# MAXIM-ADC1.net
KiCad netlist of a schematic drawn in Altium Designer
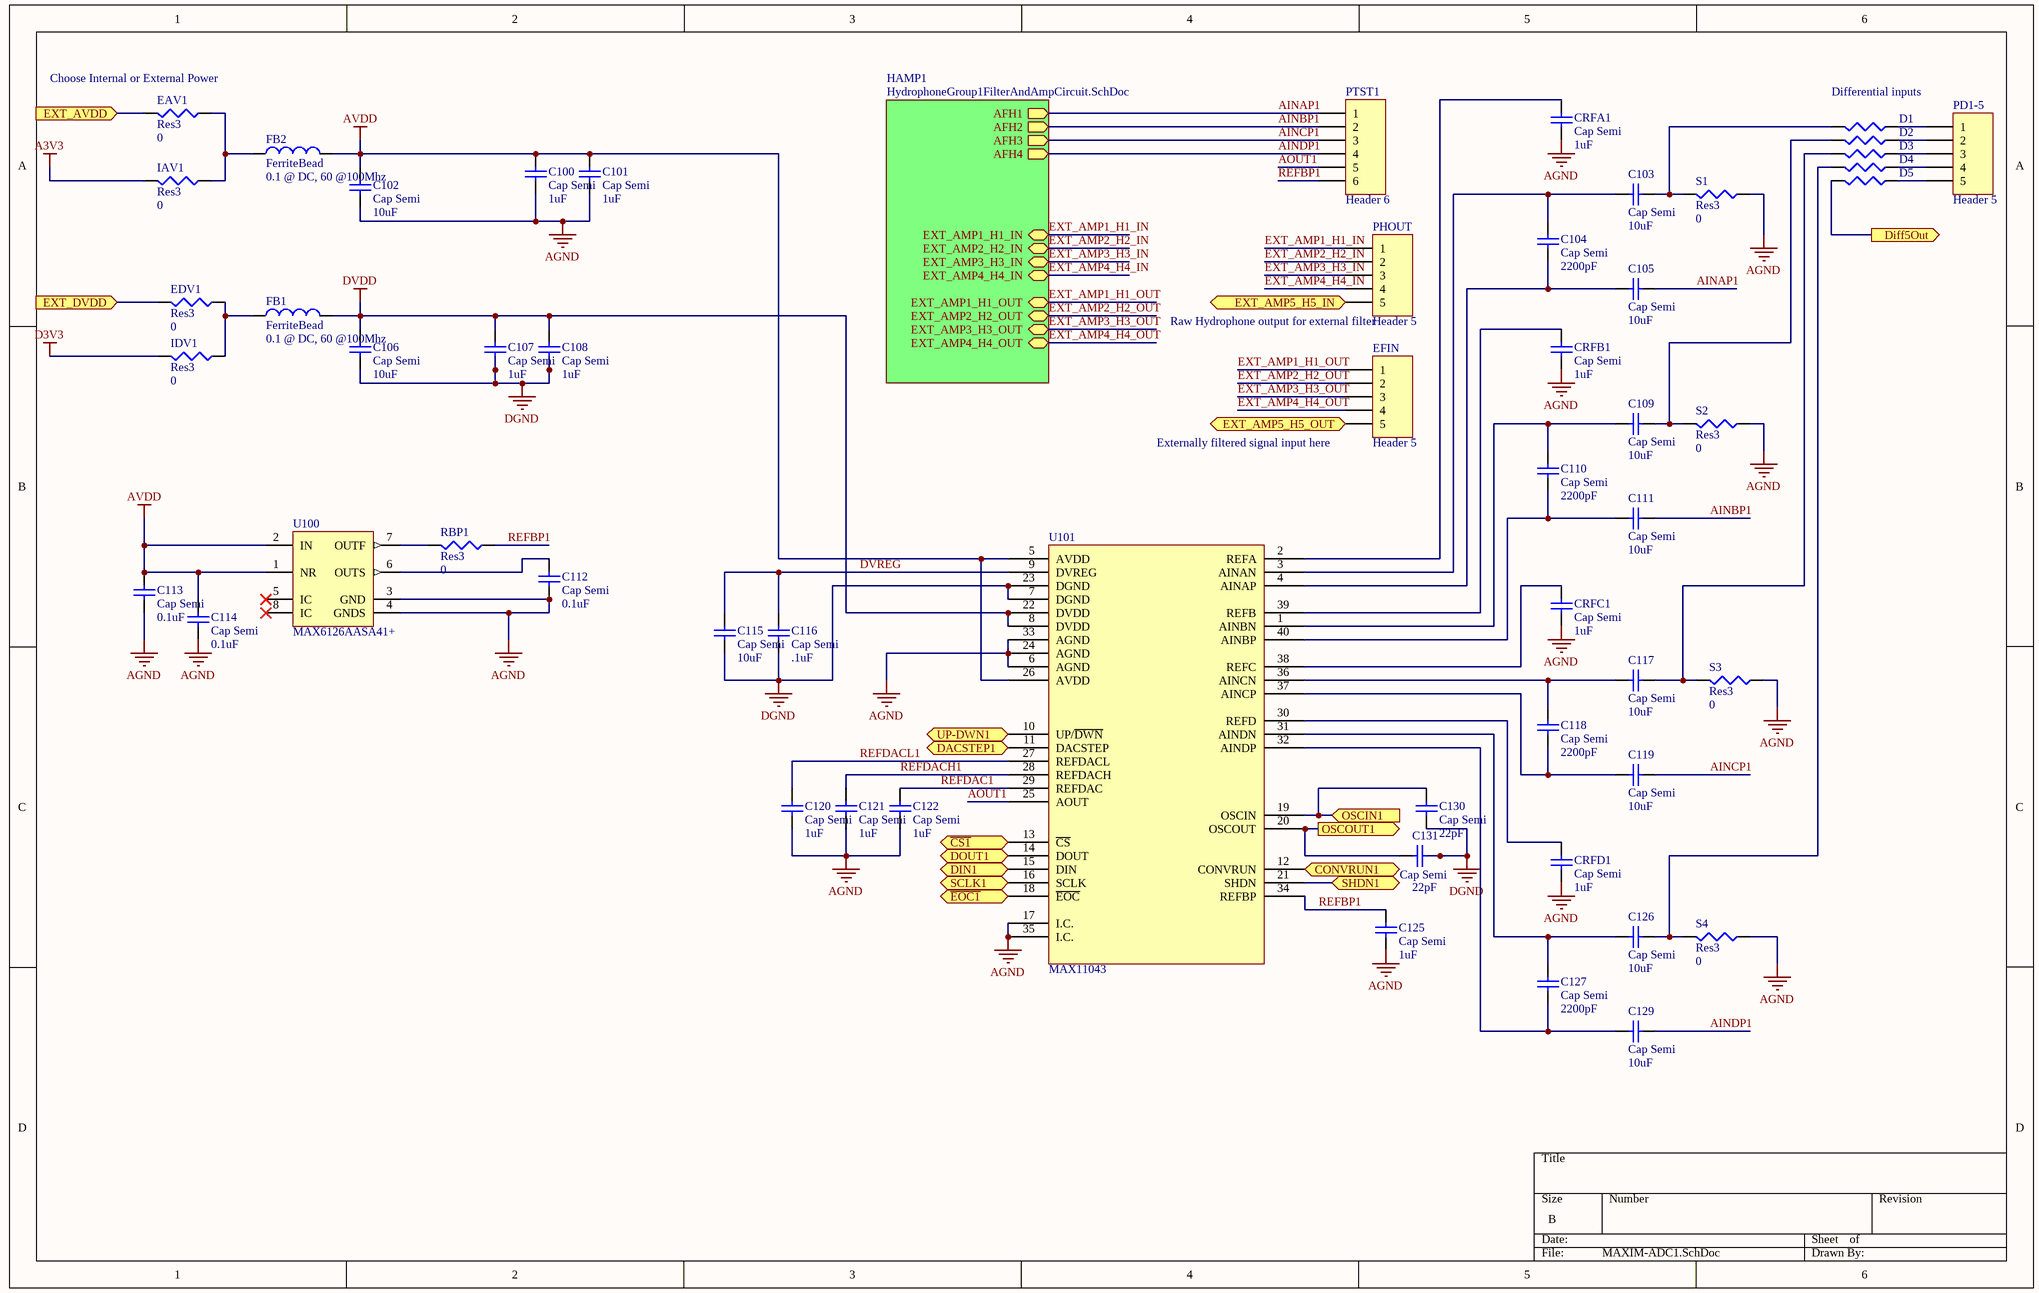
[diagram p0: MAXIM-ADC1.SchDoc]

(export (version "E")
  (design (tool "Eeschema 10.0.6"))
  (components
    (comp (ref "C100")
      (value "Cap Semi")
      (footprint "1608[0603]")
      (description "Capacitor (Semiconductor SIM Model)")
      (fields (field (name "ALTIUM_VALUE") "1uF") (field (name "PUBLISHER") "Altium Limited"))
      (libsource (lib "Miscellaneous Devices") (part "Cap Semi"))
    )
    (comp (ref "C101")
      (value "Cap Semi")
      (footprint "1608[0603]")
      (description "Capacitor (Semiconductor SIM Model)")
      (fields (field (name "ALTIUM_VALUE") "1uF") (field (name "PUBLISHER") "Altium Limited"))
      (libsource (lib "Miscellaneous Devices") (part "Cap Semi"))
    )
    (comp (ref "C102")
      (value "Cap Semi")
      (footprint "1608[0603]")
      (description "Capacitor (Semiconductor SIM Model)")
      (fields (field (name "ALTIUM_VALUE") "10uF") (field (name "PUBLISHER") "Altium Limited"))
      (libsource (lib "Miscellaneous Devices") (part "Cap Semi"))
    )
    (comp (ref "C103")
      (value "Cap Semi")
      (footprint "1608[0603]")
      (description "Capacitor (Semiconductor SIM Model)")
      (fields (field (name "ALTIUM_VALUE") "10uF") (field (name "PUBLISHER") "Altium Limited"))
      (libsource (lib "Miscellaneous Devices") (part "Cap Semi"))
    )
    (comp (ref "C104")
      (value "Cap Semi")
      (footprint "1608[0603]")
      (description "Capacitor (Semiconductor SIM Model)")
      (fields (field (name "ALTIUM_VALUE") "2200pF") (field (name "PUBLISHER") "Altium Limited"))
      (libsource (lib "Miscellaneous Devices") (part "Cap Semi"))
    )
    (comp (ref "C105")
      (value "Cap Semi")
      (footprint "1608[0603]")
      (description "Capacitor (Semiconductor SIM Model)")
      (fields (field (name "ALTIUM_VALUE") "10uF") (field (name "PUBLISHER") "Altium Limited"))
      (libsource (lib "Miscellaneous Devices") (part "Cap Semi"))
    )
    (comp (ref "C106")
      (value "Cap Semi")
      (footprint "1608[0603]")
      (description "Capacitor (Semiconductor SIM Model)")
      (fields (field (name "ALTIUM_VALUE") "10uF") (field (name "PUBLISHER") "Altium Limited"))
      (libsource (lib "Miscellaneous Devices") (part "Cap Semi"))
    )
    (comp (ref "C107")
      (value "Cap Semi")
      (footprint "1608[0603]")
      (description "Capacitor (Semiconductor SIM Model)")
      (fields (field (name "ALTIUM_VALUE") "1uF") (field (name "PUBLISHER") "Altium Limited"))
      (libsource (lib "Miscellaneous Devices") (part "Cap Semi"))
    )
    (comp (ref "C108")
      (value "Cap Semi")
      (footprint "1608[0603]")
      (description "Capacitor (Semiconductor SIM Model)")
      (fields (field (name "ALTIUM_VALUE") "1uF") (field (name "PUBLISHER") "Altium Limited"))
      (libsource (lib "Miscellaneous Devices") (part "Cap Semi"))
    )
    (comp (ref "C109")
      (value "Cap Semi")
      (footprint "1608[0603]")
      (description "Capacitor (Semiconductor SIM Model)")
      (fields (field (name "ALTIUM_VALUE") "10uF") (field (name "PUBLISHER") "Altium Limited"))
      (libsource (lib "Miscellaneous Devices") (part "Cap Semi"))
    )
    (comp (ref "C110")
      (value "Cap Semi")
      (footprint "1608[0603]")
      (description "Capacitor (Semiconductor SIM Model)")
      (fields (field (name "ALTIUM_VALUE") "2200pF") (field (name "PUBLISHER") "Altium Limited"))
      (libsource (lib "Miscellaneous Devices") (part "Cap Semi"))
    )
    (comp (ref "C111")
      (value "Cap Semi")
      (footprint "1608[0603]")
      (description "Capacitor (Semiconductor SIM Model)")
      (fields (field (name "ALTIUM_VALUE") "10uF") (field (name "PUBLISHER") "Altium Limited"))
      (libsource (lib "Miscellaneous Devices") (part "Cap Semi"))
    )
    (comp (ref "C112")
      (value "Cap Semi")
      (footprint "1608[0603]")
      (description "Capacitor (Semiconductor SIM Model)")
      (fields (field (name "ALTIUM_VALUE") "0.1uF") (field (name "PUBLISHER") "Altium Limited"))
      (libsource (lib "Miscellaneous Devices") (part "Cap Semi"))
    )
    (comp (ref "C113")
      (value "Cap Semi")
      (footprint "1608[0603]")
      (description "Capacitor (Semiconductor SIM Model)")
      (fields (field (name "ALTIUM_VALUE") "0.1uF") (field (name "PUBLISHER") "Altium Limited"))
      (libsource (lib "Miscellaneous Devices") (part "Cap Semi"))
    )
    (comp (ref "C114")
      (value "Cap Semi")
      (footprint "1608[0603]")
      (description "Capacitor (Semiconductor SIM Model)")
      (fields (field (name "ALTIUM_VALUE") "0.1uF") (field (name "PUBLISHER") "Altium Limited"))
      (libsource (lib "Miscellaneous Devices") (part "Cap Semi"))
    )
    (comp (ref "C115")
      (value "Cap Semi")
      (footprint "1608[0603]")
      (description "Capacitor (Semiconductor SIM Model)")
      (fields (field (name "ALTIUM_VALUE") "10uF") (field (name "PUBLISHER") "Altium Limited"))
      (libsource (lib "Miscellaneous Devices") (part "Cap Semi"))
    )
    (comp (ref "C116")
      (value "Cap Semi")
      (footprint "1608[0603]")
      (description "Capacitor (Semiconductor SIM Model)")
      (fields (field (name "ALTIUM_VALUE") ".1uF") (field (name "PUBLISHER") "Altium Limited"))
      (libsource (lib "Miscellaneous Devices") (part "Cap Semi"))
    )
    (comp (ref "C117")
      (value "Cap Semi")
      (footprint "1608[0603]")
      (description "Capacitor (Semiconductor SIM Model)")
      (fields (field (name "ALTIUM_VALUE") "10uF") (field (name "PUBLISHER") "Altium Limited"))
      (libsource (lib "Miscellaneous Devices") (part "Cap Semi"))
    )
    (comp (ref "C118")
      (value "Cap Semi")
      (footprint "1608[0603]")
      (description "Capacitor (Semiconductor SIM Model)")
      (fields (field (name "ALTIUM_VALUE") "2200pF") (field (name "PUBLISHER") "Altium Limited"))
      (libsource (lib "Miscellaneous Devices") (part "Cap Semi"))
    )
    (comp (ref "C119")
      (value "Cap Semi")
      (footprint "1608[0603]")
      (description "Capacitor (Semiconductor SIM Model)")
      (fields (field (name "ALTIUM_VALUE") "10uF") (field (name "PUBLISHER") "Altium Limited"))
      (libsource (lib "Miscellaneous Devices") (part "Cap Semi"))
    )
    (comp (ref "C120")
      (value "Cap Semi")
      (footprint "1608[0603]")
      (description "Capacitor (Semiconductor SIM Model)")
      (fields (field (name "ALTIUM_VALUE") "1uF") (field (name "PUBLISHER") "Altium Limited"))
      (libsource (lib "Miscellaneous Devices") (part "Cap Semi"))
    )
    (comp (ref "C121")
      (value "Cap Semi")
      (footprint "1608[0603]")
      (description "Capacitor (Semiconductor SIM Model)")
      (fields (field (name "ALTIUM_VALUE") "1uF") (field (name "PUBLISHER") "Altium Limited"))
      (libsource (lib "Miscellaneous Devices") (part "Cap Semi"))
    )
    (comp (ref "C122")
      (value "Cap Semi")
      (footprint "1608[0603]")
      (description "Capacitor (Semiconductor SIM Model)")
      (fields (field (name "ALTIUM_VALUE") "1uF") (field (name "PUBLISHER") "Altium Limited"))
      (libsource (lib "Miscellaneous Devices") (part "Cap Semi"))
    )
    (comp (ref "C125")
      (value "Cap Semi")
      (footprint "1608[0603]")
      (description "Capacitor (Semiconductor SIM Model)")
      (fields (field (name "ALTIUM_VALUE") "1uF") (field (name "PUBLISHER") "Altium Limited"))
      (libsource (lib "Miscellaneous Devices") (part "Cap Semi"))
    )
    (comp (ref "C126")
      (value "Cap Semi")
      (footprint "1608[0603]")
      (description "Capacitor (Semiconductor SIM Model)")
      (fields (field (name "ALTIUM_VALUE") "10uF") (field (name "PUBLISHER") "Altium Limited"))
      (libsource (lib "Miscellaneous Devices") (part "Cap Semi"))
    )
    (comp (ref "C127")
      (value "Cap Semi")
      (footprint "1608[0603]")
      (description "Capacitor (Semiconductor SIM Model)")
      (fields (field (name "ALTIUM_VALUE") "2200pF") (field (name "PUBLISHER") "Altium Limited"))
      (libsource (lib "Miscellaneous Devices") (part "Cap Semi"))
    )
    (comp (ref "C129")
      (value "Cap Semi")
      (footprint "1608[0603]")
      (description "Capacitor (Semiconductor SIM Model)")
      (fields (field (name "ALTIUM_VALUE") "10uF") (field (name "PUBLISHER") "Altium Limited"))
      (libsource (lib "Miscellaneous Devices") (part "Cap Semi"))
    )
    (comp (ref "C130")
      (value "Cap Semi")
      (footprint "1608[0603]")
      (description "Capacitor (Semiconductor SIM Model)")
      (fields (field (name "ALTIUM_VALUE") "22pF") (field (name "PUBLISHER") "Altium Limited"))
      (libsource (lib "Miscellaneous Devices") (part "Cap Semi"))
    )
    (comp (ref "C131")
      (value "Cap Semi")
      (footprint "1608[0603]")
      (description "Capacitor (Semiconductor SIM Model)")
      (fields (field (name "ALTIUM_VALUE") "22pF") (field (name "PUBLISHER") "Altium Limited"))
      (libsource (lib "Miscellaneous Devices") (part "Cap Semi"))
    )
    (comp (ref "CRFA1")
      (value "Cap Semi")
      (footprint "1608[0603]")
      (description "Capacitor (Semiconductor SIM Model)")
      (fields (field (name "ALTIUM_VALUE") "1uF") (field (name "PUBLISHER") "Altium Limited"))
      (libsource (lib "Miscellaneous Devices") (part "Cap Semi"))
    )
    (comp (ref "CRFB1")
      (value "Cap Semi")
      (footprint "1608[0603]")
      (description "Capacitor (Semiconductor SIM Model)")
      (fields (field (name "ALTIUM_VALUE") "1uF") (field (name "PUBLISHER") "Altium Limited"))
      (libsource (lib "Miscellaneous Devices") (part "Cap Semi"))
    )
    (comp (ref "CRFC1")
      (value "Cap Semi")
      (footprint "1608[0603]")
      (description "Capacitor (Semiconductor SIM Model)")
      (fields (field (name "ALTIUM_VALUE") "1uF") (field (name "PUBLISHER") "Altium Limited"))
      (libsource (lib "Miscellaneous Devices") (part "Cap Semi"))
    )
    (comp (ref "CRFD1")
      (value "Cap Semi")
      (footprint "1608[0603]")
      (description "Capacitor (Semiconductor SIM Model)")
      (fields (field (name "ALTIUM_VALUE") "1uF") (field (name "PUBLISHER") "Altium Limited"))
      (libsource (lib "Miscellaneous Devices") (part "Cap Semi"))
    )
    (comp (ref "D1")
      (value "Res3")
      (footprint "J1-0603")
      (description "Resistor")
      (fields (field (name "PUBLISHER") "Altium Limited"))
      (libsource (lib "Miscellaneous Devices") (part "Res3"))
    )
    (comp (ref "D2")
      (value "Res3")
      (footprint "J1-0603")
      (description "Resistor")
      (fields (field (name "PUBLISHER") "Altium Limited"))
      (libsource (lib "Miscellaneous Devices") (part "Res3"))
    )
    (comp (ref "D3")
      (value "Res3")
      (footprint "J1-0603")
      (description "Resistor")
      (fields (field (name "PUBLISHER") "Altium Limited"))
      (libsource (lib "Miscellaneous Devices") (part "Res3"))
    )
    (comp (ref "D4")
      (value "Res3")
      (footprint "J1-0603")
      (description "Resistor")
      (fields (field (name "PUBLISHER") "Altium Limited"))
      (libsource (lib "Miscellaneous Devices") (part "Res3"))
    )
    (comp (ref "D5")
      (value "Res3")
      (footprint "J1-0603")
      (description "Resistor")
      (fields (field (name "PUBLISHER") "Altium Limited"))
      (libsource (lib "Miscellaneous Devices") (part "Res3"))
    )
    (comp (ref "EAV1")
      (value "Res3")
      (footprint "J1-0603")
      (description "Resistor")
      (fields (field (name "ALTIUM_VALUE") "0") (field (name "PUBLISHER") "Altium Limited"))
      (libsource (lib "Miscellaneous Devices") (part "Res3"))
    )
    (comp (ref "EDV1")
      (value "Res3")
      (footprint "J1-0603")
      (description "Resistor")
      (fields (field (name "ALTIUM_VALUE") "0") (field (name "PUBLISHER") "Altium Limited"))
      (libsource (lib "Miscellaneous Devices") (part "Res3"))
    )
    (comp (ref "EFIN")
      (value "Header 5")
      (footprint "HDR1X5")
      (description "Header, 5-Pin")
      (fields (field (name "PUBLISHER") "Altium Limited"))
      (libsource (lib "Miscellaneous Connectors") (part "Header 5"))
    )
    (comp (ref "FB1")
      (value "FerriteBead")
      (footprint "0603")
      (description "Inductor")
      (fields
        (field (name "ALTIUM_VALUE") "0.1 @ DC, 60 @100Mhz")
        (field (name "PUBLISHER") "Altium Limited")
      )
      (libsource (lib "Miscellaneous Devices") (part "Inductor"))
    )
    (comp (ref "FB2")
      (value "FerriteBead")
      (footprint "0603")
      (description "Inductor")
      (fields
        (field (name "ALTIUM_VALUE") "0.1 @ DC, 60 @100Mhz")
        (field (name "PUBLISHER") "Altium Limited")
      )
      (libsource (lib "Miscellaneous Devices") (part "Inductor"))
    )
    (comp (ref "IAV1")
      (value "Res3")
      (footprint "J1-0603")
      (description "Resistor")
      (fields (field (name "ALTIUM_VALUE") "0") (field (name "PUBLISHER") "Altium Limited"))
      (libsource (lib "Miscellaneous Devices") (part "Res3"))
    )
    (comp (ref "IDV1")
      (value "Res3")
      (footprint "J1-0603")
      (description "Resistor")
      (fields (field (name "ALTIUM_VALUE") "0") (field (name "PUBLISHER") "Altium Limited"))
      (libsource (lib "Miscellaneous Devices") (part "Res3"))
    )
    (comp (ref "PD1-5")
      (value "Header 5")
      (footprint "HDR1X5")
      (description "Header, 5-Pin")
      (fields (field (name "PUBLISHER") "Altium Limited"))
      (libsource (lib "Miscellaneous Connectors") (part "Header 5"))
    )
    (comp (ref "PHOUT")
      (value "Header 5")
      (footprint "HDR1X5")
      (description "Header, 5-Pin")
      (fields (field (name "PUBLISHER") "Altium Limited"))
      (libsource (lib "Miscellaneous Connectors") (part "Header 5"))
    )
    (comp (ref "PTST1")
      (value "Header 6")
      (footprint "HDR1X6")
      (description "ADC1 signal test")
      (fields (field (name "PUBLISHER") "Altium Limited"))
      (libsource (lib "Miscellaneous Connectors") (part "Header 6"))
    )
    (comp (ref "RBP1")
      (value "Res3")
      (footprint "J1-0603")
      (description "Resistor")
      (fields (field (name "ALTIUM_VALUE") "0") (field (name "PUBLISHER") "Altium Limited"))
      (libsource (lib "Miscellaneous Devices") (part "Res3"))
    )
    (comp (ref "S1")
      (value "Res3")
      (footprint "J1-0603")
      (description "Resistor")
      (fields (field (name "ALTIUM_VALUE") "0") (field (name "PUBLISHER") "Altium Limited"))
      (libsource (lib "Miscellaneous Devices") (part "Res3"))
    )
    (comp (ref "S2")
      (value "Res3")
      (footprint "J1-0603")
      (description "Resistor")
      (fields (field (name "ALTIUM_VALUE") "0") (field (name "PUBLISHER") "Altium Limited"))
      (libsource (lib "Miscellaneous Devices") (part "Res3"))
    )
    (comp (ref "S3")
      (value "Res3")
      (footprint "J1-0603")
      (description "Resistor")
      (fields (field (name "ALTIUM_VALUE") "0") (field (name "PUBLISHER") "Altium Limited"))
      (libsource (lib "Miscellaneous Devices") (part "Res3"))
    )
    (comp (ref "S4")
      (value "Res3")
      (footprint "J1-0603")
      (description "Resistor")
      (fields (field (name "ALTIUM_VALUE") "0") (field (name "PUBLISHER") "Altium Limited"))
      (libsource (lib "Miscellaneous Devices") (part "Res3"))
    )
    (comp (ref "U100")
      (value "MAX6126AASA41+")
      (footprint "MAXM-S8+4_L")
      (fields (field (name "MANUFACTURER") "Maxim"))
      (libsource (lib "Altium Content Vault") (part "CMP-0977-00016-1"))
    )
    (comp (ref "U101")
      (value "MAX11043")
      (footprint "QFN50P600X600X80_HS-41N")
      (libsource (lib "Max11043") (part "MAX11043"))
    )
  )
  (nets
    (net (code "1") (name "/AINAP1") (class "Default")
      (node (ref "C105") (pin "1") (pinfunction "1_1") (pintype "passive"))
      (node (ref "PTST1") (pin "1") (pinfunction "1_1") (pintype "passive"))
    )
    (net (code "2") (name "/AINBP1") (class "Default")
      (node (ref "C111") (pin "1") (pinfunction "1_1") (pintype "passive"))
      (node (ref "PTST1") (pin "2") (pinfunction "2_2") (pintype "passive"))
    )
    (net (code "3") (name "/AINCP1") (class "Default")
      (node (ref "C119") (pin "1") (pinfunction "1_1") (pintype "passive"))
      (node (ref "PTST1") (pin "3") (pinfunction "3_3") (pintype "passive"))
    )
    (net (code "4") (name "/AINDP1") (class "Default")
      (node (ref "C129") (pin "1") (pinfunction "1_1") (pintype "passive"))
      (node (ref "PTST1") (pin "4") (pinfunction "4_4") (pintype "passive"))
    )
    (net (code "5") (name "/AOUT1") (class "Default")
      (node (ref "PTST1") (pin "5") (pinfunction "5_5") (pintype "passive"))
      (node (ref "U101") (pin "25") (pinfunction "AOUT_25") (pintype "passive"))
    )
    (net (code "6") (name "/CONVRUN1") (class "Default")
      (node (ref "U101") (pin "12") (pinfunction "CONVRUN_12") (pintype "passive"))
    )
    (net (code "7") (name "/DACSTEP1") (class "Default")
      (node (ref "U101") (pin "11") (pinfunction "DACSTEP_11") (pintype "passive"))
    )
    (net (code "8") (name "/DIN1") (class "Default")
      (node (ref "U101") (pin "15") (pinfunction "DIN_15") (pintype "passive"))
    )
    (net (code "9") (name "/DOUT1") (class "Default")
      (node (ref "U101") (pin "14") (pinfunction "DOUT_14") (pintype "passive"))
    )
    (net (code "10") (name "/DVREG") (class "Default")
      (node (ref "C115") (pin "1") (pinfunction "1_1") (pintype "passive"))
      (node (ref "C116") (pin "1") (pinfunction "1_1") (pintype "passive"))
      (node (ref "U101") (pin "9") (pinfunction "DVREG_9") (pintype "passive"))
    )
    (net (code "11") (name "/Diff5Out") (class "Default")
      (node (ref "D5") (pin "2") (pinfunction "2_2") (pintype "passive"))
    )
    (net (code "12") (name "/EXT_AMP1_H1_IN") (class "Default")
      (node (ref "PHOUT") (pin "1") (pinfunction "1_1") (pintype "passive"))
    )
    (net (code "13") (name "/EXT_AMP1_H1_OUT") (class "Default")
      (node (ref "EFIN") (pin "1") (pinfunction "1_1") (pintype "passive"))
    )
    (net (code "14") (name "/EXT_AMP2_H2_IN") (class "Default")
      (node (ref "PHOUT") (pin "2") (pinfunction "2_2") (pintype "passive"))
    )
    (net (code "15") (name "/EXT_AMP2_H2_OUT") (class "Default")
      (node (ref "EFIN") (pin "2") (pinfunction "2_2") (pintype "passive"))
    )
    (net (code "16") (name "/EXT_AMP3_H3_IN") (class "Default")
      (node (ref "PHOUT") (pin "3") (pinfunction "3_3") (pintype "passive"))
    )
    (net (code "17") (name "/EXT_AMP3_H3_OUT") (class "Default")
      (node (ref "EFIN") (pin "3") (pinfunction "3_3") (pintype "passive"))
    )
    (net (code "18") (name "/EXT_AMP4_H4_IN") (class "Default")
      (node (ref "PHOUT") (pin "4") (pinfunction "4_4") (pintype "passive"))
    )
    (net (code "19") (name "/EXT_AMP4_H4_OUT") (class "Default")
      (node (ref "EFIN") (pin "4") (pinfunction "4_4") (pintype "passive"))
    )
    (net (code "20") (name "/EXT_AMP5_H5_IN") (class "Default")
      (node (ref "PHOUT") (pin "5") (pinfunction "5_5") (pintype "passive"))
    )
    (net (code "21") (name "/EXT_AMP5_H5_OUT") (class "Default")
      (node (ref "EFIN") (pin "5") (pinfunction "5_5") (pintype "passive"))
    )
    (net (code "22") (name "/EXT_AVDD") (class "Default")
      (node (ref "EAV1") (pin "2") (pinfunction "2_2") (pintype "passive"))
    )
    (net (code "23") (name "/EXT_DVDD") (class "Default")
      (node (ref "EDV1") (pin "2") (pinfunction "2_2") (pintype "passive"))
    )
    (net (code "24") (name "/OSCIN1") (class "Default")
      (node (ref "C130") (pin "1") (pinfunction "1_1") (pintype "passive"))
      (node (ref "U101") (pin "19") (pinfunction "OSCIN_19") (pintype "passive"))
    )
    (net (code "25") (name "/OSCOUT1") (class "Default")
      (node (ref "C131") (pin "1") (pinfunction "1_1") (pintype "passive"))
      (node (ref "U101") (pin "20") (pinfunction "OSCOUT_20") (pintype "passive"))
    )
    (net (code "26") (name "/REFBP1") (class "Default")
      (node (ref "C125") (pin "1") (pinfunction "1_1") (pintype "passive"))
      (node (ref "PTST1") (pin "6") (pinfunction "6_6") (pintype "passive"))
      (node (ref "RBP1") (pin "1") (pinfunction "1_1") (pintype "passive"))
      (node (ref "U101") (pin "34") (pinfunction "REFBP_34") (pintype "passive"))
    )
    (net (code "27") (name "/REFDAC1") (class "Default")
      (node (ref "C122") (pin "2") (pinfunction "2_2") (pintype "passive"))
      (node (ref "U101") (pin "29") (pinfunction "REFDAC_29") (pintype "passive"))
    )
    (net (code "28") (name "/REFDACH1") (class "Default")
      (node (ref "C121") (pin "1") (pinfunction "1_1") (pintype "passive"))
      (node (ref "U101") (pin "28") (pinfunction "REFDACH_28") (pintype "passive"))
    )
    (net (code "29") (name "/REFDACL1") (class "Default")
      (node (ref "C120") (pin "2") (pinfunction "2_2") (pintype "passive"))
      (node (ref "U101") (pin "27") (pinfunction "REFDACL_27") (pintype "passive"))
    )
    (net (code "30") (name "/SCLK1") (class "Default")
      (node (ref "U101") (pin "16") (pinfunction "SCLK_16") (pintype "passive"))
    )
    (net (code "31") (name "/SHDN1") (class "Default")
      (node (ref "U101") (pin "21") (pinfunction "SHDN_21") (pintype "passive"))
    )
    (net (code "32") (name "/UP-DWN1") (class "Default")
      (node (ref "U101") (pin "10") (pinfunction "UP/~{DWN}_10") (pintype "passive"))
    )
    (net (code "33") (name "/~{CS1}") (class "Default")
      (node (ref "U101") (pin "13") (pinfunction "~{CS}_13") (pintype "passive"))
    )
    (net (code "34") (name "/~{EOC1}") (class "Default")
      (node (ref "U101") (pin "18") (pinfunction "~{EOC}_18") (pintype "passive"))
    )
    (net (code "35") (name "A3V3") (class "Default")
      (node (ref "IAV1") (pin "2") (pinfunction "2_2") (pintype "passive"))
    )
    (net (code "36") (name "AGND") (class "Default")
      (node (ref "C100") (pin "2") (pinfunction "2_2") (pintype "passive"))
      (node (ref "C101") (pin "2") (pinfunction "2_2") (pintype "passive"))
      (node (ref "C102") (pin "2") (pinfunction "2_2") (pintype "passive"))
      (node (ref "C112") (pin "2") (pinfunction "2_2") (pintype "passive"))
      (node (ref "C113") (pin "2") (pinfunction "2_2") (pintype "passive"))
      (node (ref "C114") (pin "2") (pinfunction "2_2") (pintype "passive"))
      (node (ref "C120") (pin "1") (pinfunction "1_1") (pintype "passive"))
      (node (ref "C121") (pin "2") (pinfunction "2_2") (pintype "passive"))
      (node (ref "C122") (pin "1") (pinfunction "1_1") (pintype "passive"))
      (node (ref "C125") (pin "2") (pinfunction "2_2") (pintype "passive"))
      (node (ref "CRFA1") (pin "1") (pinfunction "1_1") (pintype "passive"))
      (node (ref "CRFB1") (pin "1") (pinfunction "1_1") (pintype "passive"))
      (node (ref "CRFC1") (pin "1") (pinfunction "1_1") (pintype "passive"))
      (node (ref "CRFD1") (pin "1") (pinfunction "1_1") (pintype "passive"))
      (node (ref "S1") (pin "1") (pinfunction "1_1") (pintype "passive"))
      (node (ref "S2") (pin "1") (pinfunction "1_1") (pintype "passive"))
      (node (ref "S3") (pin "1") (pinfunction "1_1") (pintype "passive"))
      (node (ref "S4") (pin "1") (pinfunction "1_1") (pintype "passive"))
      (node (ref "U100") (pin "3") (pinfunction "GND_3") (pintype "power_in"))
      (node (ref "U100") (pin "4") (pinfunction "GNDS_4") (pintype "power_in"))
      (node (ref "U101") (pin "17") (pinfunction "I.C._17") (pintype "passive"))
      (node (ref "U101") (pin "24") (pinfunction "AGND_24") (pintype "passive"))
      (node (ref "U101") (pin "33") (pinfunction "AGND_33") (pintype "passive"))
      (node (ref "U101") (pin "35") (pinfunction "I.C._35") (pintype "passive"))
      (node (ref "U101") (pin "6") (pinfunction "AGND_6") (pintype "passive"))
    )
    (net (code "37") (name "AVDD") (class "Default")
      (node (ref "C100") (pin "1") (pinfunction "1_1") (pintype "passive"))
      (node (ref "C101") (pin "1") (pinfunction "1_1") (pintype "passive"))
      (node (ref "C102") (pin "1") (pinfunction "1_1") (pintype "passive"))
      (node (ref "C113") (pin "1") (pinfunction "1_1") (pintype "passive"))
      (node (ref "C114") (pin "1") (pinfunction "1_1") (pintype "passive"))
      (node (ref "FB2") (pin "2") (pinfunction "2_2") (pintype "passive"))
      (node (ref "U100") (pin "1") (pinfunction "NR_1") (pintype "passive"))
      (node (ref "U100") (pin "2") (pinfunction "IN_2") (pintype "power_in"))
      (node (ref "U101") (pin "26") (pinfunction "AVDD_26") (pintype "passive"))
      (node (ref "U101") (pin "5") (pinfunction "AVDD_5") (pintype "passive"))
    )
    (net (code "38") (name "D3V3") (class "Default")
      (node (ref "IDV1") (pin "2") (pinfunction "2_2") (pintype "passive"))
    )
    (net (code "39") (name "DGND") (class "Default")
      (node (ref "C106") (pin "2") (pinfunction "2_2") (pintype "passive"))
      (node (ref "C107") (pin "2") (pinfunction "2_2") (pintype "passive"))
      (node (ref "C108") (pin "2") (pinfunction "2_2") (pintype "passive"))
      (node (ref "C115") (pin "2") (pinfunction "2_2") (pintype "passive"))
      (node (ref "C116") (pin "2") (pinfunction "2_2") (pintype "passive"))
      (node (ref "C130") (pin "2") (pinfunction "2_2") (pintype "passive"))
      (node (ref "C131") (pin "2") (pinfunction "2_2") (pintype "passive"))
      (node (ref "U101") (pin "23") (pinfunction "DGND_23") (pintype "passive"))
      (node (ref "U101") (pin "7") (pinfunction "DGND_7") (pintype "passive"))
    )
    (net (code "40") (name "DVDD") (class "Default")
      (node (ref "C106") (pin "1") (pinfunction "1_1") (pintype "passive"))
      (node (ref "C107") (pin "1") (pinfunction "1_1") (pintype "passive"))
      (node (ref "C108") (pin "1") (pinfunction "1_1") (pintype "passive"))
      (node (ref "FB1") (pin "2") (pinfunction "2_2") (pintype "passive"))
      (node (ref "U101") (pin "22") (pinfunction "DVDD_22") (pintype "passive"))
      (node (ref "U101") (pin "8") (pinfunction "DVDD_8") (pintype "passive"))
    )
    (net (code "41") (name "Net-(C103-Pad1)") (class "Default")
      (node (ref "C103") (pin "1") (pinfunction "1_1") (pintype "passive"))
      (node (ref "D1") (pin "2") (pinfunction "2_2") (pintype "passive"))
      (node (ref "S1") (pin "2") (pinfunction "2_2") (pintype "passive"))
    )
    (net (code "42") (name "Net-(C109-Pad1)") (class "Default")
      (node (ref "C109") (pin "1") (pinfunction "1_1") (pintype "passive"))
      (node (ref "D2") (pin "2") (pinfunction "2_2") (pintype "passive"))
      (node (ref "S2") (pin "2") (pinfunction "2_2") (pintype "passive"))
    )
    (net (code "43") (name "Net-(C117-Pad1)") (class "Default")
      (node (ref "C117") (pin "1") (pinfunction "1_1") (pintype "passive"))
      (node (ref "D3") (pin "2") (pinfunction "2_2") (pintype "passive"))
      (node (ref "S3") (pin "2") (pinfunction "2_2") (pintype "passive"))
    )
    (net (code "44") (name "Net-(C126-Pad1)") (class "Default")
      (node (ref "C126") (pin "1") (pinfunction "1_1") (pintype "passive"))
      (node (ref "D4") (pin "2") (pinfunction "2_2") (pintype "passive"))
      (node (ref "S4") (pin "2") (pinfunction "2_2") (pintype "passive"))
    )
    (net (code "45") (name "Net-(D1-Pad1)") (class "Default")
      (node (ref "D1") (pin "1") (pinfunction "1_1") (pintype "passive"))
      (node (ref "PD1-5") (pin "1") (pinfunction "1_1") (pintype "passive"))
    )
    (net (code "46") (name "Net-(D2-Pad1)") (class "Default")
      (node (ref "D2") (pin "1") (pinfunction "1_1") (pintype "passive"))
      (node (ref "PD1-5") (pin "2") (pinfunction "2_2") (pintype "passive"))
    )
    (net (code "47") (name "Net-(D3-Pad1)") (class "Default")
      (node (ref "D3") (pin "1") (pinfunction "1_1") (pintype "passive"))
      (node (ref "PD1-5") (pin "3") (pinfunction "3_3") (pintype "passive"))
    )
    (net (code "48") (name "Net-(D4-Pad1)") (class "Default")
      (node (ref "D4") (pin "1") (pinfunction "1_1") (pintype "passive"))
      (node (ref "PD1-5") (pin "4") (pinfunction "4_4") (pintype "passive"))
    )
    (net (code "49") (name "Net-(D5-Pad1)") (class "Default")
      (node (ref "D5") (pin "1") (pinfunction "1_1") (pintype "passive"))
      (node (ref "PD1-5") (pin "5") (pinfunction "5_5") (pintype "passive"))
    )
    (net (code "50") (name "Net-(EAV1-Pad1)") (class "Default")
      (node (ref "EAV1") (pin "1") (pinfunction "1_1") (pintype "passive"))
      (node (ref "FB2") (pin "1") (pinfunction "1_1") (pintype "passive"))
      (node (ref "IAV1") (pin "1") (pinfunction "1_1") (pintype "passive"))
    )
    (net (code "51") (name "Net-(EDV1-Pad1)") (class "Default")
      (node (ref "EDV1") (pin "1") (pinfunction "1_1") (pintype "passive"))
      (node (ref "FB1") (pin "1") (pinfunction "1_1") (pintype "passive"))
      (node (ref "IDV1") (pin "1") (pinfunction "1_1") (pintype "passive"))
    )
    (net (code "52") (name "Net-(U100-OUTF)") (class "Default")
      (node (ref "RBP1") (pin "2") (pinfunction "2_2") (pintype "passive"))
      (node (ref "U100") (pin "7") (pinfunction "OUTF_7") (pintype "output"))
    )
    (net (code "53") (name "Net-(U100-OUTS)") (class "Default")
      (node (ref "C112") (pin "1") (pinfunction "1_1") (pintype "passive"))
      (node (ref "U100") (pin "6") (pinfunction "OUTS_6") (pintype "output"))
    )
    (net (code "54") (name "Net-(U101-AINAN)") (class "Default")
      (node (ref "C103") (pin "2") (pinfunction "2_2") (pintype "passive"))
      (node (ref "C104") (pin "2") (pinfunction "2_2") (pintype "passive"))
      (node (ref "U101") (pin "3") (pinfunction "AINAN_3") (pintype "passive"))
    )
    (net (code "55") (name "Net-(U101-AINAP)") (class "Default")
      (node (ref "C104") (pin "1") (pinfunction "1_1") (pintype "passive"))
      (node (ref "C105") (pin "2") (pinfunction "2_2") (pintype "passive"))
      (node (ref "U101") (pin "4") (pinfunction "AINAP_4") (pintype "passive"))
    )
    (net (code "56") (name "Net-(U101-AINBN)") (class "Default")
      (node (ref "C109") (pin "2") (pinfunction "2_2") (pintype "passive"))
      (node (ref "C110") (pin "2") (pinfunction "2_2") (pintype "passive"))
      (node (ref "U101") (pin "1") (pinfunction "AINBN_1") (pintype "passive"))
    )
    (net (code "57") (name "Net-(U101-AINBP)") (class "Default")
      (node (ref "C110") (pin "1") (pinfunction "1_1") (pintype "passive"))
      (node (ref "C111") (pin "2") (pinfunction "2_2") (pintype "passive"))
      (node (ref "U101") (pin "40") (pinfunction "AINBP_40") (pintype "passive"))
    )
    (net (code "58") (name "Net-(U101-AINCN)") (class "Default")
      (node (ref "C117") (pin "2") (pinfunction "2_2") (pintype "passive"))
      (node (ref "C118") (pin "2") (pinfunction "2_2") (pintype "passive"))
      (node (ref "U101") (pin "36") (pinfunction "AINCN_36") (pintype "passive"))
    )
    (net (code "59") (name "Net-(U101-AINCP)") (class "Default")
      (node (ref "C118") (pin "1") (pinfunction "1_1") (pintype "passive"))
      (node (ref "C119") (pin "2") (pinfunction "2_2") (pintype "passive"))
      (node (ref "U101") (pin "37") (pinfunction "AINCP_37") (pintype "passive"))
    )
    (net (code "60") (name "Net-(U101-AINDN)") (class "Default")
      (node (ref "C126") (pin "2") (pinfunction "2_2") (pintype "passive"))
      (node (ref "C127") (pin "2") (pinfunction "2_2") (pintype "passive"))
      (node (ref "U101") (pin "31") (pinfunction "AINDN_31") (pintype "passive"))
    )
    (net (code "61") (name "Net-(U101-AINDP)") (class "Default")
      (node (ref "C127") (pin "1") (pinfunction "1_1") (pintype "passive"))
      (node (ref "C129") (pin "2") (pinfunction "2_2") (pintype "passive"))
      (node (ref "U101") (pin "32") (pinfunction "AINDP_32") (pintype "passive"))
    )
    (net (code "62") (name "Net-(U101-REFA)") (class "Default")
      (node (ref "CRFA1") (pin "2") (pinfunction "2_2") (pintype "passive"))
      (node (ref "U101") (pin "2") (pinfunction "REFA_2") (pintype "passive"))
    )
    (net (code "63") (name "Net-(U101-REFB)") (class "Default")
      (node (ref "CRFB1") (pin "2") (pinfunction "2_2") (pintype "passive"))
      (node (ref "U101") (pin "39") (pinfunction "REFB_39") (pintype "passive"))
    )
    (net (code "64") (name "Net-(U101-REFC)") (class "Default")
      (node (ref "CRFC1") (pin "2") (pinfunction "2_2") (pintype "passive"))
      (node (ref "U101") (pin "38") (pinfunction "REFC_38") (pintype "passive"))
    )
    (net (code "65") (name "Net-(U101-REFD)") (class "Default")
      (node (ref "CRFD1") (pin "2") (pinfunction "2_2") (pintype "passive"))
      (node (ref "U101") (pin "30") (pinfunction "REFD_30") (pintype "passive"))
    )
    (net (code "66") (name "unconnected-(U100-IC-Pad5)") (class "Default")
      (node (ref "U100") (pin "5") (pinfunction "IC_5") (pintype "passive+no_connect"))
    )
    (net (code "67") (name "unconnected-(U100-IC-Pad8)") (class "Default")
      (node (ref "U100") (pin "8") (pinfunction "IC_8") (pintype "passive+no_connect"))
    )
  )
)
